# ESP32.net
KiCad netlist of a schematic drawn in Altium Designer
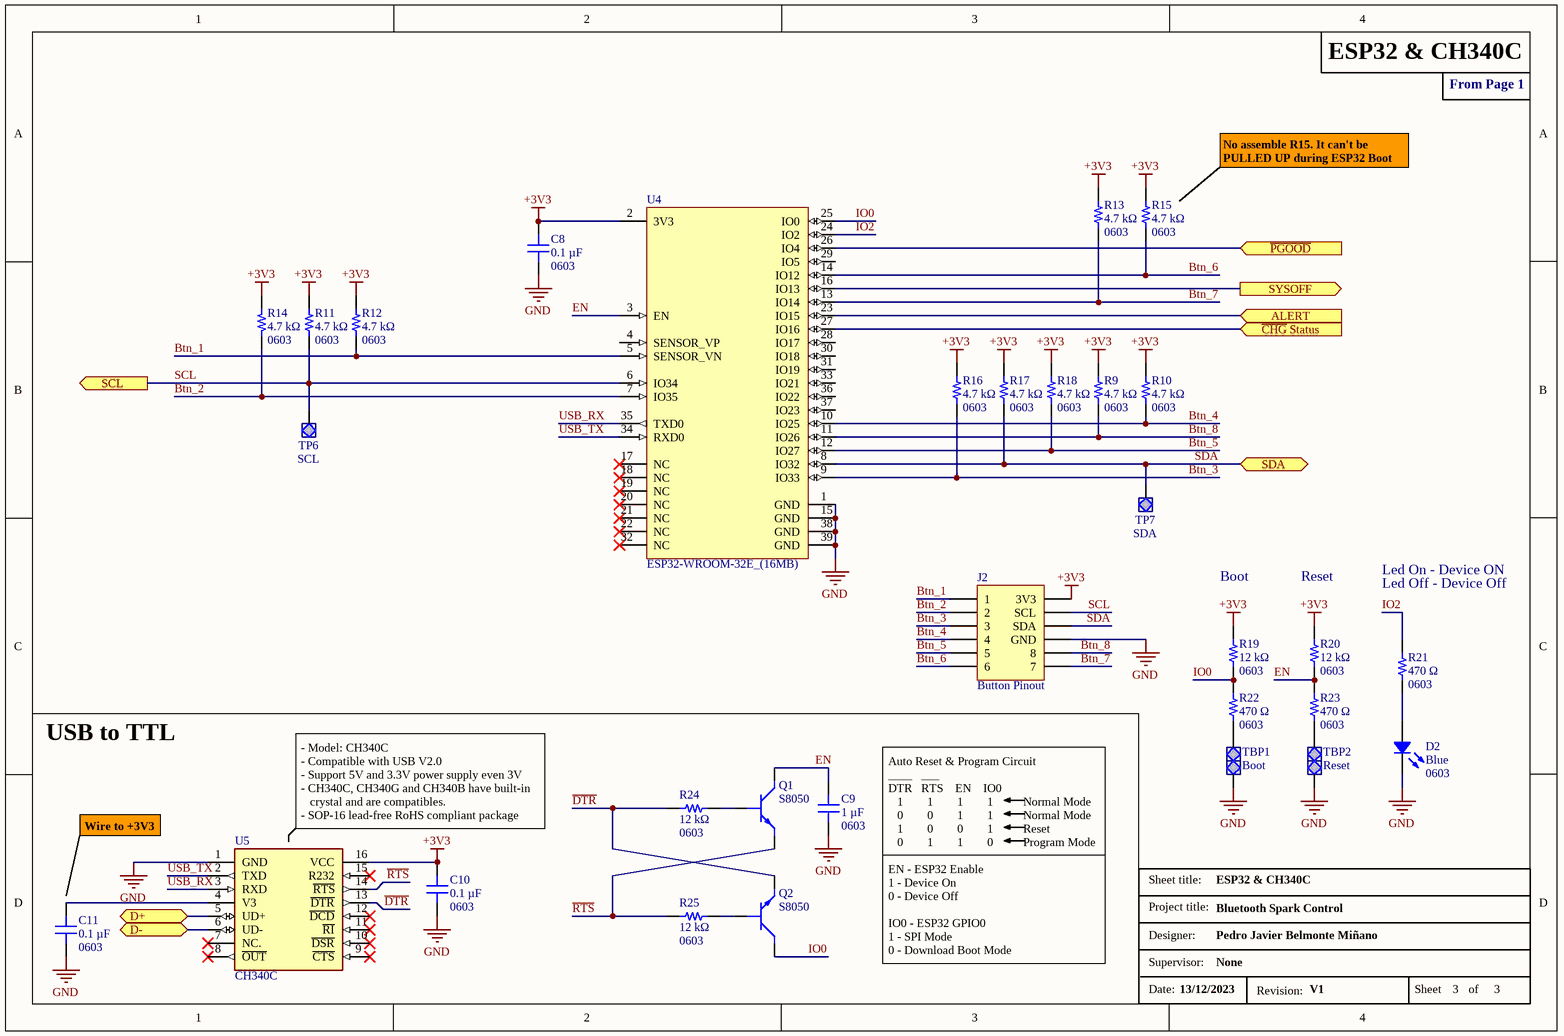
[diagram p0: ESP32.SchDoc]

(export (version "E")
  (design (tool "Eeschema 10.0.6"))
  (components
    (comp (ref "C8")
      (value "0.1 µF")
      (footprint "CAP 0603_1608")
      (description "CAP CER 0.1UF 10V X7R 0603")
      (fields
        (field (name "PART NUMBER") "100X14W104MV4T")
        (field (name "MANUFACTURER") "Johanson Dielectrics Inc.")
        (field (name "DEVICE PACKAGE") "0603")
      )
      (libsource (lib "SparkControl") (part "100X14W104MV4T"))
    )
    (comp (ref "C9")
      (value "1 µF")
      (footprint "CAP 0603_1608")
      (description "CAP CER 1UF 25V X7R 0603")
      (fields
        (field (name "PART NUMBER") "0603B105K250CT")
        (field (name "MANUFACTURER") "Walsin Technology Corporation")
        (field (name "DEVICE PACKAGE") "0603")
      )
      (libsource (lib "SparkControl") (part "0603B105K250CT"))
    )
    (comp (ref "C10")
      (value "0.1 µF")
      (footprint "CAP 0603_1608")
      (description "CAP CER 0.1UF 10V X7R 0603")
      (fields
        (field (name "PART NUMBER") "100X14W104MV4T")
        (field (name "MANUFACTURER") "Johanson Dielectrics Inc.")
        (field (name "DEVICE PACKAGE") "0603")
      )
      (libsource (lib "SparkControl") (part "100X14W104MV4T"))
    )
    (comp (ref "C11")
      (value "0.1 µF")
      (footprint "CAP 0603_1608")
      (description "CAP CER 0.1UF 10V X7R 0603")
      (fields
        (field (name "PART NUMBER") "100X14W104MV4T")
        (field (name "MANUFACTURER") "Johanson Dielectrics Inc.")
        (field (name "DEVICE PACKAGE") "0603")
      )
      (libsource (lib "SparkControl") (part "100X14W104MV4T"))
    )
    (comp (ref "D2")
      (value "Blue")
      (footprint "LED 0603_1608 BLUE")
      (description "LED BLUE 0603 SMD")
      (fields
        (field (name "PART NUMBER") "VLMB1300-GS08")
        (field (name "MANUFACTURER") "Vishay Semiconductor Opto Division")
        (field (name "SIZE") "0603")
      )
      (libsource (lib "SparkControl") (part "LED"))
    )
    (comp (ref "J2")
      (value "Button Pinout")
      (footprint "PINOUT")
      (libsource (lib "SparkControl") (part "Button Pinout"))
    )
    (comp (ref "Q1")
      (value "S8050")
      (footprint "SOT95P240X115-3N")
      (description "Transistor")
      (libsource (lib "SparkControl") (part "S8050"))
    )
    (comp (ref "Q2")
      (value "S8050")
      (footprint "SOT95P240X115-3N")
      (description "Transistor")
      (libsource (lib "SparkControl") (part "S8050"))
    )
    (comp (ref "R9")
      (value "4.7 kΩ")
      (footprint "RES 0603_1608")
      (description "RES SMD 4.7K OHM 0.1% 1/10W 0603")
      (fields
        (field (name "PART NUMBER") "ERA-3AEB472V")
        (field (name "MANUFACTURER") "Panasonic Electronic Components")
        (field (name "DEVICE PACKAGE") "0603")
      )
      (libsource (lib "SparkControl") (part "ERA-3AEB472V"))
    )
    (comp (ref "R10")
      (value "4.7 kΩ")
      (footprint "RES 0603_1608")
      (description "RES SMD 4.7K OHM 0.1% 1/10W 0603")
      (fields
        (field (name "PART NUMBER") "ERA-3AEB472V")
        (field (name "MANUFACTURER") "Panasonic Electronic Components")
        (field (name "DEVICE PACKAGE") "0603")
      )
      (libsource (lib "SparkControl") (part "ERA-3AEB472V"))
    )
    (comp (ref "R11")
      (value "4.7 kΩ")
      (footprint "RES 0603_1608")
      (description "RES SMD 4.7K OHM 0.1% 1/10W 0603")
      (fields
        (field (name "PART NUMBER") "ERA-3AEB472V")
        (field (name "MANUFACTURER") "Panasonic Electronic Components")
        (field (name "DEVICE PACKAGE") "0603")
      )
      (libsource (lib "SparkControl") (part "ERA-3AEB472V"))
    )
    (comp (ref "R12")
      (value "4.7 kΩ")
      (footprint "RES 0603_1608")
      (description "RES SMD 4.7K OHM 0.1% 1/10W 0603")
      (fields
        (field (name "PART NUMBER") "ERA-3AEB472V")
        (field (name "MANUFACTURER") "Panasonic Electronic Components")
        (field (name "DEVICE PACKAGE") "0603")
      )
      (libsource (lib "SparkControl") (part "ERA-3AEB472V"))
    )
    (comp (ref "R13")
      (value "4.7 kΩ")
      (footprint "RES 0603_1608")
      (description "RES SMD 4.7K OHM 0.1% 1/10W 0603")
      (fields
        (field (name "PART NUMBER") "ERA-3AEB472V")
        (field (name "MANUFACTURER") "Panasonic Electronic Components")
        (field (name "DEVICE PACKAGE") "0603")
      )
      (libsource (lib "SparkControl") (part "ERA-3AEB472V"))
    )
    (comp (ref "R14")
      (value "4.7 kΩ")
      (footprint "RES 0603_1608")
      (description "RES SMD 4.7K OHM 0.1% 1/10W 0603")
      (fields
        (field (name "PART NUMBER") "ERA-3AEB472V")
        (field (name "MANUFACTURER") "Panasonic Electronic Components")
        (field (name "DEVICE PACKAGE") "0603")
      )
      (libsource (lib "SparkControl") (part "ERA-3AEB472V"))
    )
    (comp (ref "R15")
      (value "4.7 kΩ")
      (footprint "RES 0603_1608")
      (description "RES SMD 4.7K OHM 0.1% 1/10W 0603")
      (fields
        (field (name "PART NUMBER") "ERA-3AEB472V")
        (field (name "MANUFACTURER") "Panasonic Electronic Components")
        (field (name "DEVICE PACKAGE") "0603")
      )
      (libsource (lib "SparkControl") (part "ERA-3AEB472V"))
    )
    (comp (ref "R16")
      (value "4.7 kΩ")
      (footprint "RES 0603_1608")
      (description "RES SMD 4.7K OHM 0.1% 1/10W 0603")
      (fields
        (field (name "PART NUMBER") "ERA-3AEB472V")
        (field (name "MANUFACTURER") "Panasonic Electronic Components")
        (field (name "DEVICE PACKAGE") "0603")
      )
      (libsource (lib "SparkControl") (part "ERA-3AEB472V"))
    )
    (comp (ref "R17")
      (value "4.7 kΩ")
      (footprint "RES 0603_1608")
      (description "RES SMD 4.7K OHM 0.1% 1/10W 0603")
      (fields
        (field (name "PART NUMBER") "ERA-3AEB472V")
        (field (name "MANUFACTURER") "Panasonic Electronic Components")
        (field (name "DEVICE PACKAGE") "0603")
      )
      (libsource (lib "SparkControl") (part "ERA-3AEB472V"))
    )
    (comp (ref "R18")
      (value "4.7 kΩ")
      (footprint "RES 0603_1608")
      (description "RES SMD 4.7K OHM 0.1% 1/10W 0603")
      (fields
        (field (name "PART NUMBER") "ERA-3AEB472V")
        (field (name "MANUFACTURER") "Panasonic Electronic Components")
        (field (name "DEVICE PACKAGE") "0603")
      )
      (libsource (lib "SparkControl") (part "ERA-3AEB472V"))
    )
    (comp (ref "R19")
      (value "12 kΩ")
      (footprint "RES 0603_1608")
      (description "RES 12K OHM 5% 1/10W 0603")
      (fields
        (field (name "PART NUMBER") "RMCF0603JT12K0")
        (field (name "MANUFACTURER") "Stackpole Electronics Inc")
        (field (name "SIZE") "0603")
      )
      (libsource (lib "SparkControl") (part "RMCF0603JT12K0"))
    )
    (comp (ref "R20")
      (value "12 kΩ")
      (footprint "RES 0603_1608")
      (description "RES 12K OHM 5% 1/10W 0603")
      (fields
        (field (name "PART NUMBER") "RMCF0603JT12K0")
        (field (name "MANUFACTURER") "Stackpole Electronics Inc")
        (field (name "SIZE") "0603")
      )
      (libsource (lib "SparkControl") (part "RMCF0603JT12K0"))
    )
    (comp (ref "R21")
      (value "470 Ω")
      (footprint "RES 0603_1608")
      (description "RES 470 OHM 5% 1/10W 0603")
      (fields
        (field (name "PART NUMBER") "RMCF0603JT470R")
        (field (name "MANUFACTURER") "Stackpole Electronics Inc")
        (field (name "SIZE") "0603")
      )
      (libsource (lib "SparkControl") (part "RMCF0603JT470R"))
    )
    (comp (ref "R22")
      (value "470 Ω")
      (footprint "RES 0603_1608")
      (description "RES 470 OHM 5% 1/10W 0603")
      (fields
        (field (name "PART NUMBER") "RMCF0603JT470R")
        (field (name "MANUFACTURER") "Stackpole Electronics Inc")
        (field (name "SIZE") "0603")
      )
      (libsource (lib "SparkControl") (part "RMCF0603JT470R"))
    )
    (comp (ref "R23")
      (value "470 Ω")
      (footprint "RES 0603_1608")
      (description "RES 470 OHM 5% 1/10W 0603")
      (fields
        (field (name "PART NUMBER") "RMCF0603JT470R")
        (field (name "MANUFACTURER") "Stackpole Electronics Inc")
        (field (name "SIZE") "0603")
      )
      (libsource (lib "SparkControl") (part "RMCF0603JT470R"))
    )
    (comp (ref "R24")
      (value "12 kΩ")
      (footprint "RES 0603_1608")
      (description "RES 12K OHM 5% 1/10W 0603")
      (fields
        (field (name "PART NUMBER") "RMCF0603JT12K0")
        (field (name "MANUFACTURER") "Stackpole Electronics Inc")
        (field (name "SIZE") "0603")
      )
      (libsource (lib "SparkControl") (part "RMCF0603JT12K0"))
    )
    (comp (ref "R25")
      (value "12 kΩ")
      (footprint "RES 0603_1608")
      (description "RES 12K OHM 5% 1/10W 0603")
      (fields
        (field (name "PART NUMBER") "RMCF0603JT12K0")
        (field (name "MANUFACTURER") "Stackpole Electronics Inc")
        (field (name "SIZE") "0603")
      )
      (libsource (lib "SparkControl") (part "RMCF0603JT12K0"))
    )
    (comp (ref "TBP1")
      (value "Boot")
      (footprint "Tweezer-bridgeable Pads")
      (description "Tweezer-Bridgeabled Pads")
      (libsource (lib "SparkControl") (part "Tweezer-Bridgeabled Pads"))
    )
    (comp (ref "TBP2")
      (value "Reset")
      (footprint "Tweezer-bridgeable Pads")
      (description "Tweezer-Bridgeabled Pads")
      (libsource (lib "SparkControl") (part "Tweezer-Bridgeabled Pads"))
    )
    (comp (ref "TP6")
      (value "SCL")
      (footprint "TestPoint")
      (description "TestPoint")
      (libsource (lib "SparkControl") (part "TestPoint"))
    )
    (comp (ref "TP7")
      (value "SDA")
      (footprint "TestPoint")
      (description "TestPoint")
      (libsource (lib "SparkControl") (part "TestPoint"))
    )
    (comp (ref "U4")
      (value "ESP32-WROOM-32E_(16MB)")
      (footprint "XCVR_ESP32-WROOM-32E_(16MB)")
      (fields (field (name "MP") "ESP32-WROOM-32E (16MB)") (field (name "MF") "Espressif Systems"))
      (libsource (lib "SparkControl") (part "ESP32-WROOM-32E_(16MB)"))
    )
    (comp (ref "U5")
      (value "CH340C")
      (footprint "SOIC127P600X180-16N")
      (description "USB to serial chip CH340")
      (fields (field (name "MF") "WCH"))
      (libsource (lib "SparkControl") (part "CH340C"))
    )
  )
  (nets
    (net (code "1") (name "+3V3") (class "Default")
      (node (ref "C10") (pin "2") (pinfunction "2_2") (pintype "passive"))
      (node (ref "C8") (pin "2") (pinfunction "2_2") (pintype "passive"))
      (node (ref "J2") (pin "12") (pinfunction "3V3_12") (pintype "passive"))
      (node (ref "R10") (pin "2") (pinfunction "2_2") (pintype "passive"))
      (node (ref "R11") (pin "2") (pinfunction "2_2") (pintype "passive"))
      (node (ref "R12") (pin "2") (pinfunction "2_2") (pintype "passive"))
      (node (ref "R13") (pin "2") (pinfunction "2_2") (pintype "passive"))
      (node (ref "R14") (pin "2") (pinfunction "2_2") (pintype "passive"))
      (node (ref "R15") (pin "2") (pinfunction "2_2") (pintype "passive"))
      (node (ref "R16") (pin "2") (pinfunction "2_2") (pintype "passive"))
      (node (ref "R17") (pin "2") (pinfunction "2_2") (pintype "passive"))
      (node (ref "R18") (pin "2") (pinfunction "2_2") (pintype "passive"))
      (node (ref "R19") (pin "1") (pinfunction "1_1") (pintype "passive"))
      (node (ref "R20") (pin "1") (pinfunction "1_1") (pintype "passive"))
      (node (ref "R9") (pin "2") (pinfunction "2_2") (pintype "passive"))
      (node (ref "U4") (pin "2") (pinfunction "3V3_2") (pintype "power_in"))
      (node (ref "U5") (pin "16") (pinfunction "VCC_16") (pintype "power_in"))
    )
    (net (code "2") (name "/ALERT") (class "Default")
      (node (ref "U4") (pin "23") (pinfunction "IO15_23") (pintype "bidirectional"))
    )
    (net (code "3") (name "/Btn_1") (class "Default")
      (node (ref "J2") (pin "1") (pinfunction "1_1") (pintype "passive"))
      (node (ref "R12") (pin "1") (pinfunction "1_1") (pintype "passive"))
      (node (ref "U4") (pin "5") (pinfunction "SENSOR_VN_5") (pintype "input"))
    )
    (net (code "4") (name "/Btn_2") (class "Default")
      (node (ref "J2") (pin "2") (pinfunction "2_2") (pintype "passive"))
      (node (ref "R14") (pin "1") (pinfunction "1_1") (pintype "passive"))
      (node (ref "U4") (pin "7") (pinfunction "IO35_7") (pintype "input"))
    )
    (net (code "5") (name "/Btn_3") (class "Default")
      (node (ref "J2") (pin "3") (pinfunction "3_3") (pintype "passive"))
      (node (ref "R16") (pin "1") (pinfunction "1_1") (pintype "passive"))
      (node (ref "U4") (pin "9") (pinfunction "IO33_9") (pintype "bidirectional"))
    )
    (net (code "6") (name "/Btn_4") (class "Default")
      (node (ref "J2") (pin "4") (pinfunction "4_4") (pintype "passive"))
      (node (ref "R10") (pin "1") (pinfunction "1_1") (pintype "passive"))
      (node (ref "U4") (pin "10") (pinfunction "IO25_10") (pintype "bidirectional"))
    )
    (net (code "7") (name "/Btn_5") (class "Default")
      (node (ref "J2") (pin "5") (pinfunction "5_5") (pintype "passive"))
      (node (ref "R18") (pin "1") (pinfunction "1_1") (pintype "passive"))
      (node (ref "U4") (pin "12") (pinfunction "IO27_12") (pintype "bidirectional"))
    )
    (net (code "8") (name "/Btn_6") (class "Default")
      (node (ref "J2") (pin "6") (pinfunction "6_6") (pintype "passive"))
      (node (ref "R15") (pin "1") (pinfunction "1_1") (pintype "passive"))
      (node (ref "U4") (pin "14") (pinfunction "IO12_14") (pintype "bidirectional"))
    )
    (net (code "9") (name "/Btn_7") (class "Default")
      (node (ref "J2") (pin "7") (pinfunction "7_7") (pintype "passive"))
      (node (ref "R13") (pin "1") (pinfunction "1_1") (pintype "passive"))
      (node (ref "U4") (pin "13") (pinfunction "IO14_13") (pintype "bidirectional"))
    )
    (net (code "10") (name "/Btn_8") (class "Default")
      (node (ref "J2") (pin "8") (pinfunction "8_8") (pintype "passive"))
      (node (ref "R9") (pin "1") (pinfunction "1_1") (pintype "passive"))
      (node (ref "U4") (pin "11") (pinfunction "IO26_11") (pintype "bidirectional"))
    )
    (net (code "11") (name "/D+") (class "Default")
      (node (ref "U5") (pin "5") (pinfunction "UD+_5") (pintype "bidirectional"))
    )
    (net (code "12") (name "/D-") (class "Default")
      (node (ref "U5") (pin "6") (pinfunction "UD-_6") (pintype "bidirectional"))
    )
    (net (code "13") (name "/EN") (class "Default")
      (node (ref "C9") (pin "2") (pinfunction "2_2") (pintype "passive"))
      (node (ref "Q1") (pin "2") (pinfunction "C_2") (pintype "passive"))
      (node (ref "R20") (pin "2") (pinfunction "2_2") (pintype "passive"))
      (node (ref "R23") (pin "1") (pinfunction "1_1") (pintype "passive"))
      (node (ref "U4") (pin "3") (pinfunction "EN_3") (pintype "input"))
    )
    (net (code "14") (name "/IO0") (class "Default")
      (node (ref "Q2") (pin "2") (pinfunction "C_2") (pintype "passive"))
      (node (ref "R19") (pin "2") (pinfunction "2_2") (pintype "passive"))
      (node (ref "R22") (pin "1") (pinfunction "1_1") (pintype "passive"))
      (node (ref "U4") (pin "25") (pinfunction "IO0_25") (pintype "bidirectional"))
    )
    (net (code "15") (name "/IO2") (class "Default")
      (node (ref "R21") (pin "1") (pinfunction "1_1") (pintype "passive"))
      (node (ref "U4") (pin "24") (pinfunction "IO2_24") (pintype "bidirectional"))
    )
    (net (code "16") (name "/SCL") (class "Default")
      (node (ref "J2") (pin "11") (pinfunction "SCL_11") (pintype "passive"))
      (node (ref "R11") (pin "1") (pinfunction "1_1") (pintype "passive"))
      (node (ref "TP6") (pin "1") (pinfunction "1_1") (pintype "passive"))
      (node (ref "U4") (pin "6") (pinfunction "IO34_6") (pintype "input"))
    )
    (net (code "17") (name "/SDA") (class "Default")
      (node (ref "J2") (pin "10") (pinfunction "SDA_10") (pintype "passive"))
      (node (ref "R17") (pin "1") (pinfunction "1_1") (pintype "passive"))
      (node (ref "TP7") (pin "1") (pinfunction "1_1") (pintype "passive"))
      (node (ref "U4") (pin "8") (pinfunction "IO32_8") (pintype "bidirectional"))
    )
    (net (code "18") (name "/SYSOFF") (class "Default")
      (node (ref "U4") (pin "16") (pinfunction "IO13_16") (pintype "bidirectional"))
    )
    (net (code "19") (name "/USB_RX") (class "Default")
      (node (ref "U4") (pin "35") (pinfunction "TXD0_35") (pintype "output"))
      (node (ref "U5") (pin "3") (pinfunction "RXD_3") (pintype "input"))
    )
    (net (code "20") (name "/USB_TX") (class "Default")
      (node (ref "U4") (pin "34") (pinfunction "RXD0_34") (pintype "input"))
      (node (ref "U5") (pin "2") (pinfunction "TXD_2") (pintype "output"))
    )
    (net (code "21") (name "/~{CHG} Status") (class "Default")
      (node (ref "U4") (pin "27") (pinfunction "IO16_27") (pintype "bidirectional"))
    )
    (net (code "22") (name "/~{DTR}") (class "Default")
      (node (ref "Q2") (pin "3") (pinfunction "E_3") (pintype "passive"))
      (node (ref "R24") (pin "1") (pinfunction "1_1") (pintype "passive"))
      (node (ref "U5") (pin "13") (pinfunction "~{DTR}_13") (pintype "output"))
    )
    (net (code "23") (name "/~{PGOOD}") (class "Default")
      (node (ref "U4") (pin "26") (pinfunction "IO4_26") (pintype "bidirectional"))
    )
    (net (code "24") (name "/~{RTS}") (class "Default")
      (node (ref "Q1") (pin "3") (pinfunction "E_3") (pintype "passive"))
      (node (ref "R25") (pin "1") (pinfunction "1_1") (pintype "passive"))
      (node (ref "U5") (pin "14") (pinfunction "~{RTS}_14") (pintype "output"))
    )
    (net (code "25") (name "GND") (class "Default")
      (node (ref "C10") (pin "1") (pinfunction "1_1") (pintype "passive"))
      (node (ref "C11") (pin "1") (pinfunction "1_1") (pintype "passive"))
      (node (ref "C8") (pin "1") (pinfunction "1_1") (pintype "passive"))
      (node (ref "C9") (pin "1") (pinfunction "1_1") (pintype "passive"))
      (node (ref "D2") (pin "2") (pinfunction "2_2") (pintype "passive"))
      (node (ref "J2") (pin "9") (pinfunction "GND_9") (pintype "passive"))
      (node (ref "TBP1") (pin "2") (pinfunction "2_2") (pintype "passive"))
      (node (ref "TBP2") (pin "2") (pinfunction "2_2") (pintype "passive"))
      (node (ref "U4") (pin "1") (pinfunction "GND_1") (pintype "power_in"))
      (node (ref "U4") (pin "15") (pinfunction "GND_15") (pintype "power_in"))
      (node (ref "U4") (pin "38") (pinfunction "GND_38") (pintype "power_in"))
      (node (ref "U4") (pin "39") (pinfunction "GND_39") (pintype "power_in"))
      (node (ref "U5") (pin "1") (pinfunction "GND_1") (pintype "power_in"))
    )
    (net (code "26") (name "Net-(D2-Pad1)") (class "Default")
      (node (ref "D2") (pin "1") (pinfunction "1_1") (pintype "passive"))
      (node (ref "R21") (pin "2") (pinfunction "2_2") (pintype "passive"))
    )
    (net (code "27") (name "Net-(Q1-B)") (class "Default")
      (node (ref "Q1") (pin "1") (pinfunction "B_1") (pintype "passive"))
      (node (ref "R24") (pin "2") (pinfunction "2_2") (pintype "passive"))
    )
    (net (code "28") (name "Net-(Q2-B)") (class "Default")
      (node (ref "Q2") (pin "1") (pinfunction "B_1") (pintype "passive"))
      (node (ref "R25") (pin "2") (pinfunction "2_2") (pintype "passive"))
    )
    (net (code "29") (name "Net-(R22-Pad2)") (class "Default")
      (node (ref "R22") (pin "2") (pinfunction "2_2") (pintype "passive"))
      (node (ref "TBP1") (pin "1") (pinfunction "1_1") (pintype "passive"))
    )
    (net (code "30") (name "Net-(R23-Pad2)") (class "Default")
      (node (ref "R23") (pin "2") (pinfunction "2_2") (pintype "passive"))
      (node (ref "TBP2") (pin "1") (pinfunction "1_1") (pintype "passive"))
    )
    (net (code "31") (name "Net-(U5-V3)") (class "Default")
      (node (ref "C11") (pin "2") (pinfunction "2_2") (pintype "passive"))
      (node (ref "U5") (pin "4") (pinfunction "V3_4") (pintype "power_in"))
    )
    (net (code "32") (name "unconnected-(U4-IO5-Pad29)") (class "Default")
      (node (ref "U4") (pin "29") (pinfunction "IO5_29") (pintype "bidirectional"))
    )
    (net (code "33") (name "unconnected-(U4-IO17-Pad28)") (class "Default")
      (node (ref "U4") (pin "28") (pinfunction "IO17_28") (pintype "bidirectional"))
    )
    (net (code "34") (name "unconnected-(U4-IO18-Pad30)") (class "Default")
      (node (ref "U4") (pin "30") (pinfunction "IO18_30") (pintype "bidirectional"))
    )
    (net (code "35") (name "unconnected-(U4-IO19-Pad31)") (class "Default")
      (node (ref "U4") (pin "31") (pinfunction "IO19_31") (pintype "bidirectional"))
    )
    (net (code "36") (name "unconnected-(U4-IO21-Pad33)") (class "Default")
      (node (ref "U4") (pin "33") (pinfunction "IO21_33") (pintype "bidirectional"))
    )
    (net (code "37") (name "unconnected-(U4-IO22-Pad36)") (class "Default")
      (node (ref "U4") (pin "36") (pinfunction "IO22_36") (pintype "bidirectional"))
    )
    (net (code "38") (name "unconnected-(U4-IO23-Pad37)") (class "Default")
      (node (ref "U4") (pin "37") (pinfunction "IO23_37") (pintype "bidirectional"))
    )
    (net (code "39") (name "unconnected-(U4-NC-Pad17)") (class "Default")
      (node (ref "U4") (pin "17") (pinfunction "NC_17") (pintype "passive+no_connect"))
    )
    (net (code "40") (name "unconnected-(U4-NC-Pad18)") (class "Default")
      (node (ref "U4") (pin "18") (pinfunction "NC_18") (pintype "passive+no_connect"))
    )
    (net (code "41") (name "unconnected-(U4-NC-Pad19)") (class "Default")
      (node (ref "U4") (pin "19") (pinfunction "NC_19") (pintype "passive+no_connect"))
    )
    (net (code "42") (name "unconnected-(U4-NC-Pad20)") (class "Default")
      (node (ref "U4") (pin "20") (pinfunction "NC_20") (pintype "passive+no_connect"))
    )
    (net (code "43") (name "unconnected-(U4-NC-Pad21)") (class "Default")
      (node (ref "U4") (pin "21") (pinfunction "NC_21") (pintype "passive+no_connect"))
    )
    (net (code "44") (name "unconnected-(U4-NC-Pad22)") (class "Default")
      (node (ref "U4") (pin "22") (pinfunction "NC_22") (pintype "passive+no_connect"))
    )
    (net (code "45") (name "unconnected-(U4-NC-Pad32)") (class "Default")
      (node (ref "U4") (pin "32") (pinfunction "NC_32") (pintype "passive+no_connect"))
    )
    (net (code "46") (name "unconnected-(U4-SENSOR_VP-Pad4)") (class "Default")
      (node (ref "U4") (pin "4") (pinfunction "SENSOR_VP_4") (pintype "input"))
    )
    (net (code "47") (name "unconnected-(U5-NC.-Pad7)") (class "Default")
      (node (ref "U5") (pin "7") (pinfunction "NC._7") (pintype "passive+no_connect"))
    )
    (net (code "48") (name "unconnected-(U5-R232-Pad15)") (class "Default")
      (node (ref "U5") (pin "15") (pinfunction "R232_15") (pintype "input+no_connect"))
    )
    (net (code "49") (name "unconnected-(U5-~{CTS}-Pad9)") (class "Default")
      (node (ref "U5") (pin "9") (pinfunction "~{CTS}_9") (pintype "input+no_connect"))
    )
    (net (code "50") (name "unconnected-(U5-~{DCD}-Pad12)") (class "Default")
      (node (ref "U5") (pin "12") (pinfunction "~{DCD}_12") (pintype "input+no_connect"))
    )
    (net (code "51") (name "unconnected-(U5-~{DSR}-Pad10)") (class "Default")
      (node (ref "U5") (pin "10") (pinfunction "~{DSR}_10") (pintype "input+no_connect"))
    )
    (net (code "52") (name "unconnected-(U5-~{OUT}-Pad8)") (class "Default")
      (node (ref "U5") (pin "8") (pinfunction "~{OUT}_8") (pintype "output+no_connect"))
    )
    (net (code "53") (name "unconnected-(U5-~{RI}-Pad11)") (class "Default")
      (node (ref "U5") (pin "11") (pinfunction "~{RI}_11") (pintype "input+no_connect"))
    )
  )
)
